# SSD1306_SCH.net
KiCad netlist of a schematic drawn in Altium Designer
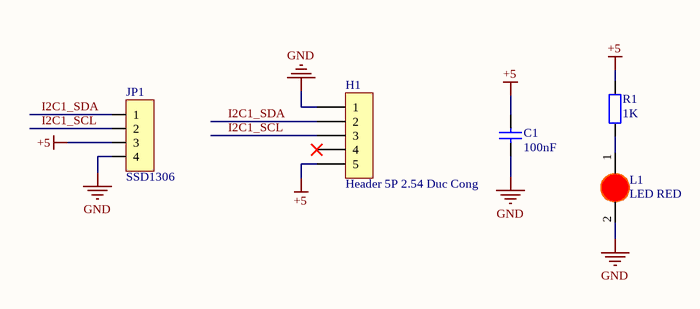
[diagram p0: SSD1306_SCH.SchDoc]

(export (version "E")
  (design (tool "Eeschema 10.0.6"))
  (components
    (comp (ref "C1")
      (value "100nF")
      (footprint "tu 0603")
      (description "Dán")
      (libsource (lib "namnt_Lib") (part "Tu 0603 104 50V 10%"))
    )
    (comp (ref "H1")
      (value "Header 5P 2.54 Duc Cong")
      (footprint "Header 5P DC 2.54")
      (description "Cắm")
      (libsource (lib "namnt_Lib") (part "Header 5P 2.54 Duc Cong"))
    )
    (comp (ref "JP1")
      (value "SSD1306")
      (footprint "JP 1x4 CT")
      (description "Cắm")
      (libsource (lib "namnt_Lib") (part "JP 1x4 2.54 Cai Thang"))
    )
    (comp (ref "L1")
      (value "LED RED")
      (footprint "LED-0805-Red")
      (description "Dán")
      (libsource (lib "namnt_Lib") (part "LED 0805 Do"))
    )
    (comp (ref "R1")
      (value "1K")
      (footprint "tro smd 0603")
      (description "Dán")
      (libsource (lib "namnt_Lib") (part "Tro 0603 1% 1k"))
    )
  )
  (nets
    (net (code "1") (name "+5") (class "Default")
      (node (ref "C1") (pin "1") (pinfunction "1_1") (pintype "passive"))
      (node (ref "H1") (pin "5") (pinfunction "5_5") (pintype "passive"))
      (node (ref "JP1") (pin "3") (pinfunction "3_3") (pintype "passive"))
      (node (ref "R1") (pin "2") (pinfunction "2_2") (pintype "passive"))
    )
    (net (code "2") (name "/I2C1_SCL") (class "Default")
      (node (ref "H1") (pin "3") (pinfunction "3_3") (pintype "passive"))
      (node (ref "JP1") (pin "2") (pinfunction "2_2") (pintype "passive"))
    )
    (net (code "3") (name "/I2C1_SDA") (class "Default")
      (node (ref "H1") (pin "2") (pinfunction "2_2") (pintype "passive"))
      (node (ref "JP1") (pin "1") (pinfunction "1_1") (pintype "passive"))
    )
    (net (code "4") (name "GND") (class "Default")
      (node (ref "C1") (pin "2") (pinfunction "2_2") (pintype "passive"))
      (node (ref "H1") (pin "1") (pinfunction "1_1") (pintype "passive"))
      (node (ref "JP1") (pin "4") (pinfunction "4_4") (pintype "passive"))
      (node (ref "L1") (pin "2") (pinfunction "K_2") (pintype "passive"))
    )
    (net (code "5") (name "Net-(L1-A)") (class "Default")
      (node (ref "L1") (pin "1") (pinfunction "A_1") (pintype "passive"))
      (node (ref "R1") (pin "1") (pinfunction "1_1") (pintype "passive"))
    )
    (net (code "6") (name "unconnected-(H1-Pad4)") (class "Default")
      (node (ref "H1") (pin "4") (pinfunction "4_4") (pintype "passive+no_connect"))
    )
  )
)
